# Astron.net
KiCad netlist of a schematic drawn in EAGLE
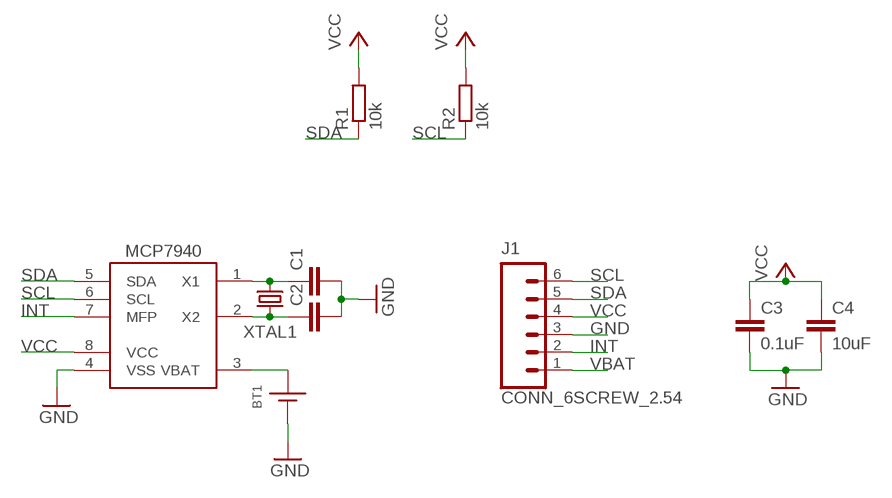
[diagram p0: schematic, sheet 1]

(export (version "E")
  (design (tool "Eeschema 10.0.6"))
  (components
    (comp (ref "BT1")
      (value "BATTERY_COIN12MM")
      (footprint "eagle-import:LINX_BAT-HLD-012-SMT")
      (fields (field (name "MF") "Linx") (field (name "MPN") "BAT-HLD-012-SMT"))
      (libsource (lib "eagle-import") (part "BATTERY_COIN12MM"))
    )
    (comp (ref "C1")
      (value "C-EUC0603")
      (footprint "eagle-import:C0603")
      (libsource (lib "eagle-import") (part "C-EUC0603"))
    )
    (comp (ref "C2")
      (value "C-EUC0603")
      (footprint "eagle-import:C0603")
      (libsource (lib "eagle-import") (part "C-EUC0603"))
    )
    (comp (ref "C3")
      (value "0.1uF")
      (footprint "eagle-import:C0603")
      (fields (field (name "MF") "Murata") (field (name "MPN") "GCM188R71E104KA57D"))
      (libsource (lib "eagle-import") (part "C-EUC06030.1UF"))
    )
    (comp (ref "C4")
      (value "10uF")
      (footprint "eagle-import:C0805")
      (fields (field (name "MF") "Murata") (field (name "MPN") "GRM21BR61C106KE15K"))
      (libsource (lib "eagle-import") (part "C-EUC080510UF"))
    )
    (comp (ref "J1")
      (value "CONN_6SCREW_2.54")
      (footprint "eagle-import:1X06_SCREW")
      (fields (field (name "MF") "OnShore") (field (name "MPN") "OSTVN06A150"))
      (libsource (lib "eagle-import") (part "CONN_6SCREW_2.54"))
    )
    (comp (ref "R1")
      (value "10k")
      (footprint "eagle-import:R0603")
      (fields (field (name "MF") "Yageo"))
      (libsource (lib "eagle-import") (part "R-EU_R0603"))
    )
    (comp (ref "R2")
      (value "10k")
      (footprint "eagle-import:R0603")
      (fields (field (name "MF") "Yageo"))
      (libsource (lib "eagle-import") (part "R-EU_R0603"))
    )
    (comp (ref "U$1")
      (value "MCP7940SOIC")
      (footprint "eagle-import:SO08")
      (fields (field (name "MF") "Microchip") (field (name "MPN") "MCP7940N-I/SN"))
      (libsource (lib "eagle-import") (part "MCP7940SOIC"))
    )
    (comp (ref "XTAL1")
      (value "CRYSTAL3.2X1.5")
      (footprint "eagle-import:CRYSTAL_3.2X1.5_2-SMD")
      (libsource (lib "eagle-import") (part "CRYSTAL3.2X1.5"))
    )
  )
  (nets
    (net (code "1") (name "/INT") (class "Default")
      (node (ref "J1") (pin "2") (pinfunction "2_2") (pintype "passive"))
      (node (ref "U$1") (pin "7") (pinfunction "MFP_7") (pintype "bidirectional"))
    )
    (net (code "2") (name "/SCL") (class "Default")
      (node (ref "J1") (pin "6") (pinfunction "6_6") (pintype "passive"))
      (node (ref "R2") (pin "1") (pinfunction "1_1") (pintype "passive"))
      (node (ref "U$1") (pin "6") (pinfunction "SCL_6") (pintype "bidirectional"))
    )
    (net (code "3") (name "/SDA") (class "Default")
      (node (ref "J1") (pin "5") (pinfunction "5_5") (pintype "passive"))
      (node (ref "R1") (pin "1") (pinfunction "1_1") (pintype "passive"))
      (node (ref "U$1") (pin "5") (pinfunction "SDA_5") (pintype "bidirectional"))
    )
    (net (code "4") (name "/VBAT") (class "Default")
      (node (ref "BT1") (pin "POWER0") (pinfunction "+_POWER0") (pintype "bidirectional"))
      (node (ref "BT1") (pin "POWER1") (pinfunction "+_POWER1") (pintype "bidirectional"))
      (node (ref "J1") (pin "1") (pinfunction "1_1") (pintype "passive"))
      (node (ref "U$1") (pin "3") (pinfunction "VBAT_3") (pintype "bidirectional"))
    )
    (net (code "5") (name "GND") (class "Default")
      (node (ref "BT1") (pin "GND") (pinfunction "-_GND") (pintype "bidirectional"))
      (node (ref "C1") (pin "2") (pinfunction "2_2") (pintype "passive"))
      (node (ref "C2") (pin "2") (pinfunction "2_2") (pintype "passive"))
      (node (ref "C3") (pin "2") (pinfunction "2_2") (pintype "passive"))
      (node (ref "C4") (pin "2") (pinfunction "2_2") (pintype "passive"))
      (node (ref "J1") (pin "3") (pinfunction "3_3") (pintype "passive"))
      (node (ref "U$1") (pin "4") (pinfunction "VSS_4") (pintype "bidirectional"))
    )
    (net (code "6") (name "Net-(U$1-X1)") (class "Default")
      (node (ref "C1") (pin "1") (pinfunction "1_1") (pintype "passive"))
      (node (ref "U$1") (pin "1") (pinfunction "X1_1") (pintype "bidirectional"))
      (node (ref "XTAL1") (pin "P$1") (pinfunction "1_P$1") (pintype "passive"))
    )
    (net (code "7") (name "Net-(U$1-X2)") (class "Default")
      (node (ref "C2") (pin "1") (pinfunction "1_1") (pintype "passive"))
      (node (ref "U$1") (pin "2") (pinfunction "X2_2") (pintype "bidirectional"))
      (node (ref "XTAL1") (pin "P$2") (pinfunction "2_P$2") (pintype "passive"))
    )
    (net (code "8") (name "VCC") (class "Default")
      (node (ref "C3") (pin "1") (pinfunction "1_1") (pintype "passive"))
      (node (ref "C4") (pin "1") (pinfunction "1_1") (pintype "passive"))
      (node (ref "J1") (pin "4") (pinfunction "4_4") (pintype "passive"))
      (node (ref "R1") (pin "2") (pinfunction "2_2") (pintype "passive"))
      (node (ref "R2") (pin "2") (pinfunction "2_2") (pintype "passive"))
      (node (ref "U$1") (pin "8") (pinfunction "VCC_8") (pintype "bidirectional"))
    )
  )
)
